# 5_CURRENT_SOURCE.net
KiCad netlist of a schematic drawn in Altium Designer
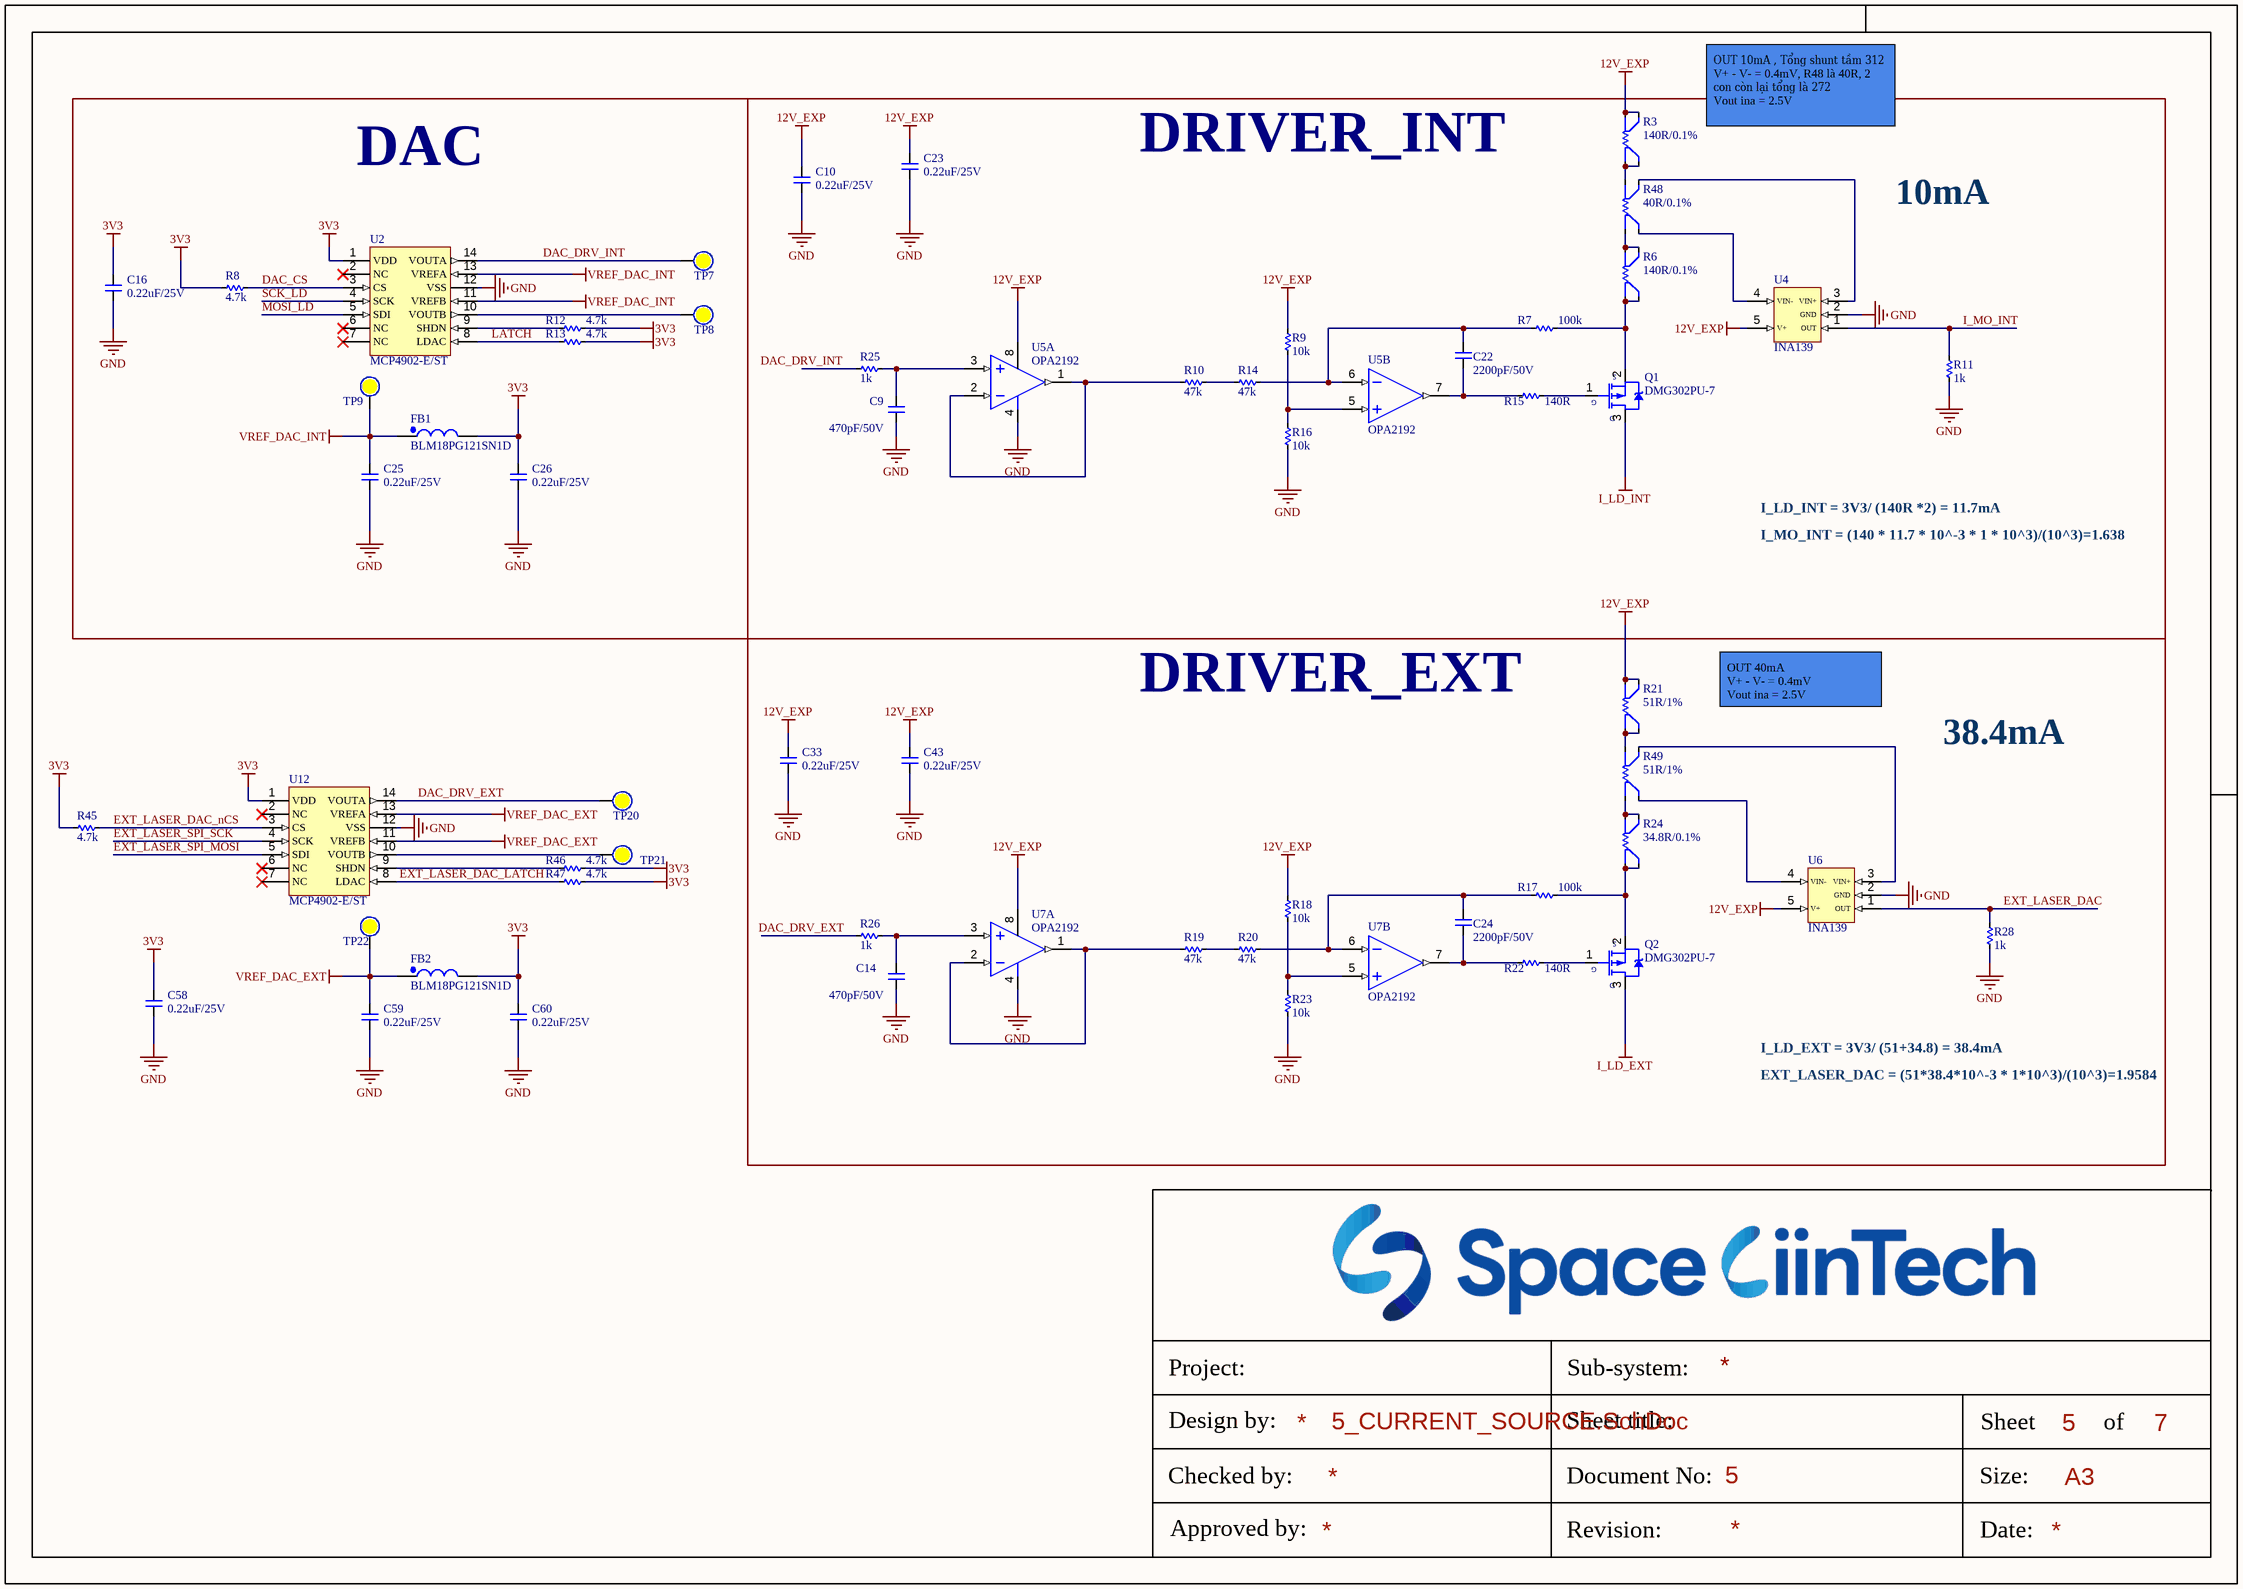
[diagram p0: 5_CURRENT_SOURCE.SchDoc]

(export (version "E")
  (design (tool "Eeschema 10.0.6"))
  (components
    (comp (ref "C9")
      (value "470pF/50V")
      (footprint "CAP_C_1608X80")
      (description "CAP")
      (libsource (lib "LABLIB") (part "_CAP_C_2"))
    )
    (comp (ref "C10")
      (value "0.22uF/25V")
      (footprint "CAP_C_1608X80")
      (description "CAP")
      (libsource (lib "LABLIB") (part "_CAP_C_2"))
    )
    (comp (ref "C14")
      (value "470pF/50V")
      (footprint "CAP_C_1608X80")
      (description "CAP")
      (libsource (lib "LABLIB") (part "_CAP_C_2"))
    )
    (comp (ref "C16")
      (value "0.22uF/25V")
      (footprint "CAP_C_1608X80")
      (description "CAP")
      (libsource (lib "LABLIB") (part "_CAP_C_2"))
    )
    (comp (ref "C22")
      (value "2200pF/50V")
      (footprint "CAP_C_1608X80")
      (description "CAP")
      (libsource (lib "LABLIB") (part "_CAP_C_2"))
    )
    (comp (ref "C23")
      (value "0.22uF/25V")
      (footprint "CAP_C_1608X80")
      (description "CAP")
      (libsource (lib "LABLIB") (part "_CAP_C_2"))
    )
    (comp (ref "C24")
      (value "2200pF/50V")
      (footprint "CAP_C_1608X80")
      (description "CAP")
      (libsource (lib "LABLIB") (part "_CAP_C_2"))
    )
    (comp (ref "C25")
      (value "0.22uF/25V")
      (footprint "CAP_C_1608X80")
      (description "CAP")
      (libsource (lib "LABLIB") (part "_CAP_C_2"))
    )
    (comp (ref "C26")
      (value "0.22uF/25V")
      (footprint "CAP_C_1608X80")
      (description "CAP")
      (libsource (lib "LABLIB") (part "_CAP_C_2"))
    )
    (comp (ref "C33")
      (value "0.22uF/25V")
      (footprint "CAP_C_1608X80")
      (description "CAP")
      (libsource (lib "LABLIB") (part "_CAP_C_2"))
    )
    (comp (ref "C43")
      (value "0.22uF/25V")
      (footprint "CAP_C_1608X80")
      (description "CAP")
      (libsource (lib "LABLIB") (part "_CAP_C_2"))
    )
    (comp (ref "C58")
      (value "0.22uF/25V")
      (footprint "CAP_C_1608X80")
      (description "CAP")
      (libsource (lib "LABLIB") (part "_CAP_C_2"))
    )
    (comp (ref "C59")
      (value "0.22uF/25V")
      (footprint "CAP_C_1608X80")
      (description "CAP")
      (libsource (lib "LABLIB") (part "_CAP_C_2"))
    )
    (comp (ref "C60")
      (value "0.22uF/25V")
      (footprint "CAP_C_1608X80")
      (description "CAP")
      (libsource (lib "LABLIB") (part "_CAP_C_2"))
    )
    (comp (ref "FB1")
      (value "BLM18PG121SN1D")
      (footprint "IND_C_1608X60")
      (libsource (lib "LABLIB") (part "_IND"))
    )
    (comp (ref "FB2")
      (value "BLM18PG121SN1D")
      (footprint "IND_C_1608X60")
      (libsource (lib "LABLIB") (part "_IND"))
    )
    (comp (ref "Q1")
      (value "DMG302PU-7")
      (footprint "SOT23-3-132")
      (libsource (lib "LASER_LIB_SCHE") (part "P_MOSFET"))
    )
    (comp (ref "Q2")
      (value "DMG302PU-7")
      (footprint "SOT23-3-132")
      (libsource (lib "LASER_LIB_SCHE") (part "P_MOSFET"))
    )
    (comp (ref "R3")
      (value "140R/0.1%")
      (footprint "RES_SMD_0603_SHUNT")
      (description "RN73R1JTTD30R0B25")
      (libsource (lib "LASER_LIB_SCHE") (part "RES_SMD_SHUNT"))
    )
    (comp (ref "R6")
      (value "140R/0.1%")
      (footprint "RES_SMD_0603_SHUNT")
      (description "RN73R1JTTD30R0B25")
      (libsource (lib "LASER_LIB_SCHE") (part "RES_SMD_SHUNT"))
    )
    (comp (ref "R7")
      (value "100k")
      (footprint "RES_C_1608X60")
      (description "RES")
      (libsource (lib "LABLIB") (part "_RES_B_2"))
    )
    (comp (ref "R8")
      (value "4.7k")
      (footprint "RES_C_1608X60")
      (description "RES")
      (libsource (lib "LABLIB") (part "_RES_B_2"))
    )
    (comp (ref "R9")
      (value "10k")
      (footprint "RES_C_1608X60")
      (description "RES")
      (libsource (lib "LABLIB") (part "_RES_B_2"))
    )
    (comp (ref "R10")
      (value "47k")
      (footprint "RES_C_1608X60")
      (description "RES")
      (libsource (lib "LABLIB") (part "_RES_B_2"))
    )
    (comp (ref "R11")
      (value "1k")
      (footprint "RES_C_1608X60")
      (description "RES")
      (libsource (lib "LABLIB") (part "_RES_B_2"))
    )
    (comp (ref "R12")
      (value "4.7k")
      (footprint "RES_C_1608X60")
      (description "RES")
      (libsource (lib "LABLIB") (part "_RES_B_2"))
    )
    (comp (ref "R13")
      (value "4.7k")
      (footprint "RES_C_1608X60")
      (description "RES")
      (libsource (lib "LABLIB") (part "_RES_B_2"))
    )
    (comp (ref "R14")
      (value "47k")
      (footprint "RES_C_1608X60")
      (description "RES")
      (libsource (lib "LABLIB") (part "_RES_B_2"))
    )
    (comp (ref "R15")
      (value "140R")
      (footprint "RES_C_1608X60")
      (description "RES")
      (libsource (lib "LABLIB") (part "_RES_B_2"))
    )
    (comp (ref "R16")
      (value "10k")
      (footprint "RES_C_1608X60")
      (description "RES")
      (libsource (lib "LABLIB") (part "_RES_B_2"))
    )
    (comp (ref "R17")
      (value "100k")
      (footprint "RES_C_1608X60")
      (description "RES")
      (libsource (lib "LABLIB") (part "_RES_B_2"))
    )
    (comp (ref "R18")
      (value "10k")
      (footprint "RES_C_1608X60")
      (description "RES")
      (libsource (lib "LABLIB") (part "_RES_B_2"))
    )
    (comp (ref "R19")
      (value "47k")
      (footprint "RES_C_1608X60")
      (description "RES")
      (libsource (lib "LABLIB") (part "_RES_B_2"))
    )
    (comp (ref "R20")
      (value "47k")
      (footprint "RES_C_1608X60")
      (description "RES")
      (libsource (lib "LABLIB") (part "_RES_B_2"))
    )
    (comp (ref "R21")
      (value "51R/1%")
      (footprint "RES_SMD_0603_SHUNT")
      (description "RT0603BRD077R5L")
      (libsource (lib "LASER_LIB_SCHE") (part "RES_SMD_SHUNT"))
    )
    (comp (ref "R22")
      (value "140R")
      (footprint "RES_C_1608X60")
      (description "RES")
      (libsource (lib "LABLIB") (part "_RES_B_2"))
    )
    (comp (ref "R23")
      (value "10k")
      (footprint "RES_C_1608X60")
      (description "RES")
      (libsource (lib "LABLIB") (part "_RES_B_2"))
    )
    (comp (ref "R24")
      (value "34.8R/0.1%")
      (footprint "RES_SMD_0603_SHUNT")
      (description "RT0603BRD077R5L")
      (libsource (lib "LASER_LIB_SCHE") (part "RES_SMD_SHUNT"))
    )
    (comp (ref "R25")
      (value "1k")
      (footprint "RES_C_1608X60")
      (description "RES")
      (libsource (lib "LABLIB") (part "_RES_B_2"))
    )
    (comp (ref "R26")
      (value "1k")
      (footprint "RES_C_1608X60")
      (description "RES")
      (libsource (lib "LABLIB") (part "_RES_B_2"))
    )
    (comp (ref "R28")
      (value "1k")
      (footprint "RES_C_1608X60")
      (description "RES")
      (libsource (lib "LABLIB") (part "_RES_B_2"))
    )
    (comp (ref "R45")
      (value "4.7k")
      (footprint "RES_C_1608X60")
      (description "RES")
      (libsource (lib "LABLIB") (part "_RES_B_2"))
    )
    (comp (ref "R46")
      (value "4.7k")
      (footprint "RES_C_1608X60")
      (description "RES")
      (libsource (lib "LABLIB") (part "_RES_B_2"))
    )
    (comp (ref "R47")
      (value "4.7k")
      (footprint "RES_C_1608X60")
      (description "RES")
      (libsource (lib "LABLIB") (part "_RES_B_2"))
    )
    (comp (ref "R48")
      (value "40R/0.1%")
      (footprint "RES_SMD_0603_SHUNT")
      (description "RN73R1JTTD30R0B25")
      (libsource (lib "LASER_LIB_SCHE") (part "RES_SMD_SHUNT"))
    )
    (comp (ref "R49")
      (value "51R/1%")
      (footprint "RES_SMD_0603_SHUNT")
      (description "RT0603BRD077R5L")
      (libsource (lib "LASER_LIB_SCHE") (part "RES_SMD_SHUNT"))
    )
    (comp (ref "TP7")
      (value "~")
      (footprint "Testpoint_80")
      (description "Test Point")
      (libsource (lib "LASER_LIB_SCHE") (part "Test Point"))
    )
    (comp (ref "TP8")
      (value "~")
      (footprint "Testpoint_80")
      (description "Test Point")
      (libsource (lib "LASER_LIB_SCHE") (part "Test Point"))
    )
    (comp (ref "TP9")
      (value "~")
      (footprint "Testpoint_80")
      (description "Test Point")
      (libsource (lib "") (part "Test Point_1"))
    )
    (comp (ref "TP20")
      (value "~")
      (footprint "Testpoint_80")
      (description "Test Point")
      (libsource (lib "LASER_LIB_SCHE") (part "Test Point"))
    )
    (comp (ref "TP21")
      (value "~")
      (footprint "Testpoint_80")
      (description "Test Point")
      (libsource (lib "LASER_LIB_SCHE") (part "Test Point"))
    )
    (comp (ref "TP22")
      (value "~")
      (footprint "Testpoint_80")
      (description "Test Point")
      (libsource (lib "") (part "Test Point_1"))
    )
    (comp (ref "U2")
      (value "MCP4902-E/ST")
      (footprint "TSSOP14")
      (libsource (lib "LASER_LIB_SCHE") (part "MCP4902"))
    )
    (comp (ref "U4")
      (value "INA139")
      (footprint "SOT23-5")
      (description "INA139NA/250")
      (libsource (lib "LASER_LIB_SCHE") (part "INA139"))
    )
    (comp (ref "U5")
      (value "OPA2192")
      (footprint "SO8")
      (description "OPA2192IDR")
      (libsource (lib "LASER_LIB_SCHE") (part "LM358"))
    )
    (comp (ref "U6")
      (value "INA139")
      (footprint "SOT23-5")
      (description "INA139NA/250")
      (libsource (lib "LASER_LIB_SCHE") (part "INA139"))
    )
    (comp (ref "U7")
      (value "OPA2192")
      (footprint "SO8")
      (description "OPA2192IDR")
      (libsource (lib "LASER_LIB_SCHE") (part "LM358"))
    )
    (comp (ref "U12")
      (value "MCP4902-E/ST")
      (footprint "TSSOP14")
      (libsource (lib "LASER_LIB_SCHE") (part "MCP4902"))
    )
  )
  (nets
    (net (code "1") (name "/DAC_CS") (class "Default")
      (node (ref "R8") (pin "2") (pinfunction "2_2") (pintype "passive"))
      (node (ref "U2") (pin "3") (pinfunction "CS_3") (pintype "input"))
    )
    (net (code "2") (name "/DAC_DRV_EXT") (class "Default")
      (node (ref "R26") (pin "1") (pinfunction "1_1") (pintype "passive"))
      (node (ref "TP20") (pin "1") (pinfunction "1_1") (pintype "passive"))
      (node (ref "U12") (pin "14") (pinfunction "VOUTA_14") (pintype "output"))
    )
    (net (code "3") (name "/DAC_DRV_INT") (class "Default")
      (node (ref "R25") (pin "1") (pinfunction "1_1") (pintype "passive"))
      (node (ref "TP7") (pin "1") (pinfunction "1_1") (pintype "passive"))
      (node (ref "U2") (pin "14") (pinfunction "VOUTA_14") (pintype "output"))
    )
    (net (code "4") (name "/EXT_LASER_DAC") (class "Default")
      (node (ref "R28") (pin "1") (pinfunction "1_1") (pintype "passive"))
      (node (ref "U6") (pin "1") (pinfunction "OUT_1") (pintype "input"))
    )
    (net (code "5") (name "/EXT_LASER_DAC_LATCH") (class "Default")
      (node (ref "R47") (pin "1") (pinfunction "1_1") (pintype "passive"))
      (node (ref "U12") (pin "8") (pinfunction "LDAC_8") (pintype "input"))
    )
    (net (code "6") (name "/EXT_LASER_DAC_nCS") (class "Default")
      (node (ref "R45") (pin "2") (pinfunction "2_2") (pintype "passive"))
      (node (ref "U12") (pin "3") (pinfunction "CS_3") (pintype "input"))
    )
    (net (code "7") (name "/EXT_LASER_SPI_MOSI") (class "Default")
      (node (ref "U12") (pin "5") (pinfunction "SDI_5") (pintype "input"))
    )
    (net (code "8") (name "/EXT_LASER_SPI_SCK") (class "Default")
      (node (ref "U12") (pin "4") (pinfunction "SCK_4") (pintype "input"))
    )
    (net (code "9") (name "/I_MO_INT") (class "Default")
      (node (ref "R11") (pin "1") (pinfunction "1_1") (pintype "passive"))
      (node (ref "U4") (pin "1") (pinfunction "OUT_1") (pintype "input"))
    )
    (net (code "10") (name "/LATCH") (class "Default")
      (node (ref "R13") (pin "1") (pinfunction "1_1") (pintype "passive"))
      (node (ref "U2") (pin "8") (pinfunction "LDAC_8") (pintype "input"))
    )
    (net (code "11") (name "/MOSI_LD") (class "Default")
      (node (ref "U2") (pin "5") (pinfunction "SDI_5") (pintype "input"))
    )
    (net (code "12") (name "/SCK_LD") (class "Default")
      (node (ref "U2") (pin "4") (pinfunction "SCK_4") (pintype "input"))
    )
    (net (code "13") (name "3V3") (class "Default")
      (node (ref "C16") (pin "2") (pinfunction "2_2") (pintype "passive"))
      (node (ref "C26") (pin "2") (pinfunction "2_2") (pintype "passive"))
      (node (ref "C58") (pin "2") (pinfunction "2_2") (pintype "passive"))
      (node (ref "C60") (pin "2") (pinfunction "2_2") (pintype "passive"))
      (node (ref "FB1") (pin "2") (pinfunction "2_2") (pintype "passive"))
      (node (ref "FB2") (pin "2") (pinfunction "2_2") (pintype "passive"))
      (node (ref "R12") (pin "2") (pinfunction "2_2") (pintype "passive"))
      (node (ref "R13") (pin "2") (pinfunction "2_2") (pintype "passive"))
      (node (ref "R45") (pin "1") (pinfunction "1_1") (pintype "passive"))
      (node (ref "R46") (pin "2") (pinfunction "2_2") (pintype "passive"))
      (node (ref "R47") (pin "2") (pinfunction "2_2") (pintype "passive"))
      (node (ref "R8") (pin "1") (pinfunction "1_1") (pintype "passive"))
      (node (ref "U12") (pin "1") (pinfunction "VDD_1") (pintype "power_in"))
      (node (ref "U2") (pin "1") (pinfunction "VDD_1") (pintype "power_in"))
    )
    (net (code "14") (name "12V_EXP") (class "Default")
      (node (ref "C10") (pin "2") (pinfunction "2_2") (pintype "passive"))
      (node (ref "C23") (pin "2") (pinfunction "2_2") (pintype "passive"))
      (node (ref "C33") (pin "2") (pinfunction "2_2") (pintype "passive"))
      (node (ref "C43") (pin "2") (pinfunction "2_2") (pintype "passive"))
      (node (ref "R18") (pin "1") (pinfunction "1_1") (pintype "passive"))
      (node (ref "R21") (pin "1") (pinfunction "1_1") (pintype "passive"))
      (node (ref "R21") (pin "3") (pinfunction "3_3") (pintype "passive"))
      (node (ref "R3") (pin "1") (pinfunction "1_1") (pintype "passive"))
      (node (ref "R3") (pin "3") (pinfunction "3_3") (pintype "passive"))
      (node (ref "R9") (pin "1") (pinfunction "1_1") (pintype "passive"))
      (node (ref "U4") (pin "5") (pinfunction "V+_5") (pintype "input"))
      (node (ref "U5") (pin "8") (pinfunction "+V_8") (pintype "passive"))
      (node (ref "U6") (pin "5") (pinfunction "V+_5") (pintype "input"))
      (node (ref "U7") (pin "8") (pinfunction "+V_8") (pintype "passive"))
    )
    (net (code "15") (name "GND") (class "Default")
      (node (ref "C10") (pin "1") (pinfunction "1_1") (pintype "passive"))
      (node (ref "C14") (pin "1") (pinfunction "1_1") (pintype "passive"))
      (node (ref "C16") (pin "1") (pinfunction "1_1") (pintype "passive"))
      (node (ref "C23") (pin "1") (pinfunction "1_1") (pintype "passive"))
      (node (ref "C25") (pin "1") (pinfunction "1_1") (pintype "passive"))
      (node (ref "C26") (pin "1") (pinfunction "1_1") (pintype "passive"))
      (node (ref "C33") (pin "1") (pinfunction "1_1") (pintype "passive"))
      (node (ref "C43") (pin "1") (pinfunction "1_1") (pintype "passive"))
      (node (ref "C58") (pin "1") (pinfunction "1_1") (pintype "passive"))
      (node (ref "C59") (pin "1") (pinfunction "1_1") (pintype "passive"))
      (node (ref "C60") (pin "1") (pinfunction "1_1") (pintype "passive"))
      (node (ref "C9") (pin "1") (pinfunction "1_1") (pintype "passive"))
      (node (ref "R11") (pin "2") (pinfunction "2_2") (pintype "passive"))
      (node (ref "R16") (pin "2") (pinfunction "2_2") (pintype "passive"))
      (node (ref "R23") (pin "2") (pinfunction "2_2") (pintype "passive"))
      (node (ref "R28") (pin "2") (pinfunction "2_2") (pintype "passive"))
      (node (ref "U12") (pin "12") (pinfunction "VSS_12") (pintype "power_in"))
      (node (ref "U2") (pin "12") (pinfunction "VSS_12") (pintype "power_in"))
      (node (ref "U4") (pin "2") (pinfunction "GND_2") (pintype "input"))
      (node (ref "U5") (pin "4") (pinfunction "-V_4") (pintype "passive"))
      (node (ref "U6") (pin "2") (pinfunction "GND_2") (pintype "input"))
      (node (ref "U7") (pin "4") (pinfunction "-V_4") (pintype "passive"))
    )
    (net (code "16") (name "I_LD_EXT") (class "Default")
      (node (ref "Q2") (pin "3") (pinfunction "D_3") (pintype "passive"))
    )
    (net (code "17") (name "I_LD_INT") (class "Default")
      (node (ref "Q1") (pin "3") (pinfunction "D_3") (pintype "passive"))
    )
    (net (code "18") (name "Net-(Q1-G)") (class "Default")
      (node (ref "Q1") (pin "1") (pinfunction "G_1") (pintype "passive"))
      (node (ref "R15") (pin "2") (pinfunction "2_2") (pintype "passive"))
    )
    (net (code "19") (name "Net-(Q1-S)") (class "Default")
      (node (ref "Q1") (pin "2") (pinfunction "S_2") (pintype "passive"))
      (node (ref "R6") (pin "2") (pinfunction "2_2") (pintype "passive"))
      (node (ref "R6") (pin "4") (pinfunction "4_4") (pintype "passive"))
      (node (ref "R7") (pin "2") (pinfunction "2_2") (pintype "passive"))
    )
    (net (code "20") (name "Net-(Q2-G)") (class "Default")
      (node (ref "Q2") (pin "1") (pinfunction "G_1") (pintype "passive"))
      (node (ref "R22") (pin "2") (pinfunction "2_2") (pintype "passive"))
    )
    (net (code "21") (name "Net-(Q2-S)") (class "Default")
      (node (ref "Q2") (pin "2") (pinfunction "S_2") (pintype "passive"))
      (node (ref "R17") (pin "2") (pinfunction "2_2") (pintype "passive"))
      (node (ref "R24") (pin "2") (pinfunction "2_2") (pintype "passive"))
      (node (ref "R24") (pin "4") (pinfunction "4_4") (pintype "passive"))
    )
    (net (code "22") (name "Net-(R3-Pad2)") (class "Default")
      (node (ref "R3") (pin "2") (pinfunction "2_2") (pintype "passive"))
      (node (ref "R3") (pin "4") (pinfunction "4_4") (pintype "passive"))
      (node (ref "R48") (pin "1") (pinfunction "1_1") (pintype "passive"))
    )
    (net (code "23") (name "Net-(R10-Pad2)") (class "Default")
      (node (ref "R10") (pin "2") (pinfunction "2_2") (pintype "passive"))
      (node (ref "R14") (pin "1") (pinfunction "1_1") (pintype "passive"))
    )
    (net (code "24") (name "Net-(R19-Pad2)") (class "Default")
      (node (ref "R19") (pin "2") (pinfunction "2_2") (pintype "passive"))
      (node (ref "R20") (pin "1") (pinfunction "1_1") (pintype "passive"))
    )
    (net (code "25") (name "Net-(R21-Pad2)") (class "Default")
      (node (ref "R21") (pin "2") (pinfunction "2_2") (pintype "passive"))
      (node (ref "R21") (pin "4") (pinfunction "4_4") (pintype "passive"))
      (node (ref "R49") (pin "1") (pinfunction "1_1") (pintype "passive"))
    )
    (net (code "26") (name "Net-(R24-Pad1)") (class "Default")
      (node (ref "R24") (pin "1") (pinfunction "1_1") (pintype "passive"))
      (node (ref "R24") (pin "3") (pinfunction "3_3") (pintype "passive"))
      (node (ref "R49") (pin "2") (pinfunction "2_2") (pintype "passive"))
    )
    (net (code "27") (name "Net-(R48-Pad2)") (class "Default")
      (node (ref "R48") (pin "2") (pinfunction "2_2") (pintype "passive"))
      (node (ref "R6") (pin "1") (pinfunction "1_1") (pintype "passive"))
      (node (ref "R6") (pin "3") (pinfunction "3_3") (pintype "passive"))
    )
    (net (code "28") (name "Net-(U2-SHDN)") (class "Default")
      (node (ref "R12") (pin "1") (pinfunction "1_1") (pintype "passive"))
      (node (ref "U2") (pin "9") (pinfunction "SHDN_9") (pintype "input"))
    )
    (net (code "29") (name "Net-(U2-VOUTB)") (class "Default")
      (node (ref "TP8") (pin "1") (pinfunction "1_1") (pintype "passive"))
      (node (ref "U2") (pin "10") (pinfunction "VOUTB_10") (pintype "output"))
    )
    (net (code "30") (name "Net-(U4-VIN+)") (class "Default")
      (node (ref "R48") (pin "3") (pinfunction "3_3") (pintype "passive"))
      (node (ref "U4") (pin "3") (pinfunction "VIN+_3") (pintype "input"))
    )
    (net (code "31") (name "Net-(U4-VIN-)") (class "Default")
      (node (ref "R48") (pin "4") (pinfunction "4_4") (pintype "passive"))
      (node (ref "U4") (pin "4") (pinfunction "VIN-_4") (pintype "input"))
    )
    (net (code "32") (name "Net-(U5A-IN+)") (class "Default")
      (node (ref "C9") (pin "2") (pinfunction "2_2") (pintype "passive"))
      (node (ref "R25") (pin "2") (pinfunction "2_2") (pintype "passive"))
      (node (ref "U5") (pin "3") (pinfunction "IN+_3") (pintype "input"))
    )
    (net (code "33") (name "Net-(U5A-IN-)") (class "Default")
      (node (ref "R10") (pin "1") (pinfunction "1_1") (pintype "passive"))
      (node (ref "U5") (pin "1") (pinfunction "OUT_1") (pintype "output"))
      (node (ref "U5") (pin "2") (pinfunction "IN-_2") (pintype "input"))
    )
    (net (code "34") (name "Net-(U5B-IN+)") (class "Default")
      (node (ref "R16") (pin "1") (pinfunction "1_1") (pintype "passive"))
      (node (ref "R9") (pin "2") (pinfunction "2_2") (pintype "passive"))
      (node (ref "U5") (pin "5") (pinfunction "IN+_5") (pintype "input"))
    )
    (net (code "35") (name "Net-(U5B-IN-)") (class "Default")
      (node (ref "C22") (pin "1") (pinfunction "1_1") (pintype "passive"))
      (node (ref "R14") (pin "2") (pinfunction "2_2") (pintype "passive"))
      (node (ref "R7") (pin "1") (pinfunction "1_1") (pintype "passive"))
      (node (ref "U5") (pin "6") (pinfunction "IN-_6") (pintype "input"))
    )
    (net (code "36") (name "Net-(U5B-OUT)") (class "Default")
      (node (ref "C22") (pin "2") (pinfunction "2_2") (pintype "passive"))
      (node (ref "R15") (pin "1") (pinfunction "1_1") (pintype "passive"))
      (node (ref "U5") (pin "7") (pinfunction "OUT_7") (pintype "output"))
    )
    (net (code "37") (name "Net-(U6-VIN+)") (class "Default")
      (node (ref "R49") (pin "3") (pinfunction "3_3") (pintype "passive"))
      (node (ref "U6") (pin "3") (pinfunction "VIN+_3") (pintype "input"))
    )
    (net (code "38") (name "Net-(U6-VIN-)") (class "Default")
      (node (ref "R49") (pin "4") (pinfunction "4_4") (pintype "passive"))
      (node (ref "U6") (pin "4") (pinfunction "VIN-_4") (pintype "input"))
    )
    (net (code "39") (name "Net-(U7A-IN+)") (class "Default")
      (node (ref "C14") (pin "2") (pinfunction "2_2") (pintype "passive"))
      (node (ref "R26") (pin "2") (pinfunction "2_2") (pintype "passive"))
      (node (ref "U7") (pin "3") (pinfunction "IN+_3") (pintype "input"))
    )
    (net (code "40") (name "Net-(U7A-IN-)") (class "Default")
      (node (ref "R19") (pin "1") (pinfunction "1_1") (pintype "passive"))
      (node (ref "U7") (pin "1") (pinfunction "OUT_1") (pintype "output"))
      (node (ref "U7") (pin "2") (pinfunction "IN-_2") (pintype "input"))
    )
    (net (code "41") (name "Net-(U7B-IN+)") (class "Default")
      (node (ref "R18") (pin "2") (pinfunction "2_2") (pintype "passive"))
      (node (ref "R23") (pin "1") (pinfunction "1_1") (pintype "passive"))
      (node (ref "U7") (pin "5") (pinfunction "IN+_5") (pintype "input"))
    )
    (net (code "42") (name "Net-(U7B-IN-)") (class "Default")
      (node (ref "C24") (pin "1") (pinfunction "1_1") (pintype "passive"))
      (node (ref "R17") (pin "1") (pinfunction "1_1") (pintype "passive"))
      (node (ref "R20") (pin "2") (pinfunction "2_2") (pintype "passive"))
      (node (ref "U7") (pin "6") (pinfunction "IN-_6") (pintype "input"))
    )
    (net (code "43") (name "Net-(U7B-OUT)") (class "Default")
      (node (ref "C24") (pin "2") (pinfunction "2_2") (pintype "passive"))
      (node (ref "R22") (pin "1") (pinfunction "1_1") (pintype "passive"))
      (node (ref "U7") (pin "7") (pinfunction "OUT_7") (pintype "output"))
    )
    (net (code "44") (name "Net-(U12-SHDN)") (class "Default")
      (node (ref "R46") (pin "1") (pinfunction "1_1") (pintype "passive"))
      (node (ref "U12") (pin "9") (pinfunction "SHDN_9") (pintype "input"))
    )
    (net (code "45") (name "Net-(U12-VOUTB)") (class "Default")
      (node (ref "TP21") (pin "1") (pinfunction "1_1") (pintype "passive"))
      (node (ref "U12") (pin "10") (pinfunction "VOUTB_10") (pintype "output"))
    )
    (net (code "46") (name "VREF_DAC_EXT") (class "Default")
      (node (ref "C59") (pin "2") (pinfunction "2_2") (pintype "passive"))
      (node (ref "FB2") (pin "1") (pinfunction "1_1") (pintype "passive"))
      (node (ref "TP22") (pin "1") (pinfunction "1_1") (pintype "passive"))
      (node (ref "U12") (pin "11") (pinfunction "VREFB_11") (pintype "input"))
      (node (ref "U12") (pin "13") (pinfunction "VREFA_13") (pintype "input"))
    )
    (net (code "47") (name "VREF_DAC_INT") (class "Default")
      (node (ref "C25") (pin "2") (pinfunction "2_2") (pintype "passive"))
      (node (ref "FB1") (pin "1") (pinfunction "1_1") (pintype "passive"))
      (node (ref "TP9") (pin "1") (pinfunction "1_1") (pintype "passive"))
      (node (ref "U2") (pin "11") (pinfunction "VREFB_11") (pintype "input"))
      (node (ref "U2") (pin "13") (pinfunction "VREFA_13") (pintype "input"))
    )
    (net (code "48") (name "unconnected-(U2-NC-Pad2)") (class "Default")
      (node (ref "U2") (pin "2") (pinfunction "NC_2") (pintype "tri_state+no_connect"))
    )
    (net (code "49") (name "unconnected-(U2-NC-Pad6)") (class "Default")
      (node (ref "U2") (pin "6") (pinfunction "NC_6") (pintype "tri_state+no_connect"))
    )
    (net (code "50") (name "unconnected-(U2-NC-Pad7)") (class "Default")
      (node (ref "U2") (pin "7") (pinfunction "NC_7") (pintype "tri_state+no_connect"))
    )
    (net (code "51") (name "unconnected-(U12-NC-Pad2)") (class "Default")
      (node (ref "U12") (pin "2") (pinfunction "NC_2") (pintype "tri_state+no_connect"))
    )
    (net (code "52") (name "unconnected-(U12-NC-Pad6)") (class "Default")
      (node (ref "U12") (pin "6") (pinfunction "NC_6") (pintype "tri_state+no_connect"))
    )
    (net (code "53") (name "unconnected-(U12-NC-Pad7)") (class "Default")
      (node (ref "U12") (pin "7") (pinfunction "NC_7") (pintype "tri_state+no_connect"))
    )
  )
)
